# esptoy_v122.net
KiCad netlist of a schematic drawn in EAGLE
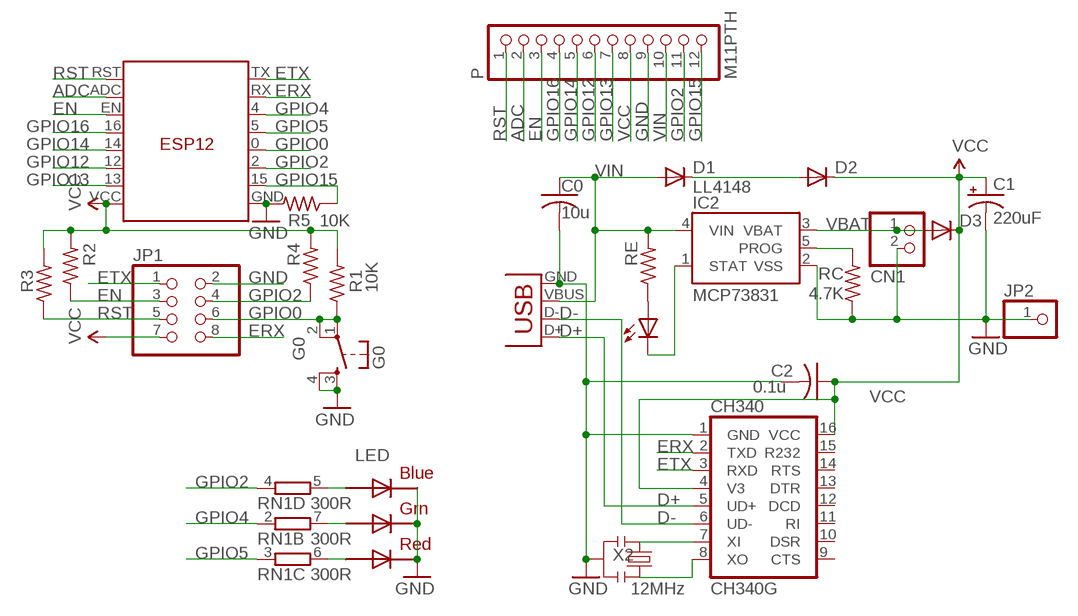
[diagram p0: schematic, sheet 1]

(export (version "E")
  (design (tool "Eeschema 10.0.6"))
  (components
    (comp (ref "C0")
      (value "10u")
      (footprint "eagle-import:C0805K")
      (libsource (lib "eagle-import") (part "adafruit2013_C-USC0805K"))
    )
    (comp (ref "C1")
      (value "220uF")
      (footprint "eagle-import:EIA7343")
      (libsource (lib "eagle-import") (part "CAP_POL7343"))
    )
    (comp (ref "C2")
      (value "0.1u")
      (footprint "eagle-import:C0603K")
      (libsource (lib "eagle-import") (part "C-USC0603K"))
    )
    (comp (ref "CH340")
      (value "CH340G")
      (footprint "eagle-import:SO16")
      (libsource (lib "eagle-import") (part "CH340G"))
    )
    (comp (ref "CHG")
      (value "0805")
      (footprint "eagle-import:CHIPLED_0805")
      (libsource (lib "eagle-import") (part "LEDCHIPLED_0805"))
    )
    (comp (ref "CN1")
      (value "JST_2PIN-SMT-RA")
      (footprint "eagle-import:JST-PH-2-SMT-RA")
      (libsource (lib "eagle-import") (part "JST_2PIN-SMT-RA"))
    )
    (comp (ref "D1")
      (value "LL4148")
      (footprint "eagle-import:SMA-DIODE")
      (libsource (lib "eagle-import") (part "DIODESMA"))
    )
    (comp (ref "D2")
      (value "DIODESMA")
      (footprint "eagle-import:SMA-DIODE")
      (libsource (lib "eagle-import") (part "DIODESMA"))
    )
    (comp (ref "D3")
      (value "DIODESMA")
      (footprint "eagle-import:SMA-DIODE")
      (libsource (lib "eagle-import") (part "DIODESMA"))
    )
    (comp (ref "G0")
      (value "G0")
      (footprint "eagle-import:TACTILE_SWITCH_SMD")
      (libsource (lib "eagle-import") (part "TAC_SWITCHSMD"))
    )
    (comp (ref "IC2")
      (value "MCP73831")
      (footprint "eagle-import:SOT23-5")
      (libsource (lib "eagle-import") (part "MCP73831"))
    )
    (comp (ref "JP1")
      (value "PINHD-2X4")
      (footprint "eagle-import:2X04")
      (libsource (lib "eagle-import") (part "PINHD-2X4"))
    )
    (comp (ref "JP2")
      (value "PINHD-1X1CB")
      (footprint "eagle-import:1X01-CLEANBIG")
      (libsource (lib "eagle-import") (part "PINHD-1X1CB"))
    )
    (comp (ref "LED")
      (value "RGBLED5050")
      (footprint "eagle-import:RGBLED5050")
      (libsource (lib "eagle-import") (part "RGBLED5050"))
    )
    (comp (ref "P")
      (value "M11PTH")
      (footprint "eagle-import:1X12-CB")
      (libsource (lib "eagle-import") (part "PINHD-1X12-CB"))
    )
    (comp (ref "R1")
      (value "10K")
      (footprint "eagle-import:R0603")
      (libsource (lib "eagle-import") (part "R-US_R0603"))
    )
    (comp (ref "R2")
      (value "R-US_R0603")
      (footprint "eagle-import:R0603")
      (libsource (lib "eagle-import") (part "R-US_R0603"))
    )
    (comp (ref "R3")
      (value "R-US_R0603")
      (footprint "eagle-import:R0603")
      (libsource (lib "eagle-import") (part "R-US_R0603"))
    )
    (comp (ref "R4")
      (value "R-US_R0603")
      (footprint "eagle-import:R0603")
      (libsource (lib "eagle-import") (part "R-US_R0603"))
    )
    (comp (ref "R5")
      (value "10K")
      (footprint "eagle-import:R0603")
      (libsource (lib "eagle-import") (part "R-US_R0603"))
    )
    (comp (ref "RC")
      (value "4.7K")
      (footprint "eagle-import:R0805")
      (libsource (lib "eagle-import") (part "adafruit2013_R-US_R0805"))
    )
    (comp (ref "RE")
      (value "R-US_R0603")
      (footprint "eagle-import:R0603")
      (libsource (lib "eagle-import") (part "R-US_R0603"))
    )
    (comp (ref "RN1")
      (value "300R")
      (footprint "eagle-import:EXB38V")
      (libsource (lib "eagle-import") (part "4R-NEXB38V"))
    )
    (comp (ref "U$1")
      (value "ESP12")
      (footprint "eagle-import:ESP12")
      (libsource (lib "eagle-import") (part "ESP12"))
    )
    (comp (ref "X1")
      (value "USBSMD")
      (footprint "eagle-import:USB-MINIB")
      (libsource (lib "eagle-import") (part "USBSMD"))
    )
    (comp (ref "X2")
      (value "12MHz")
      (footprint "eagle-import:RESONATOR-SMD")
      (libsource (lib "eagle-import") (part "RESONATORSMD"))
    )
  )
  (nets
    (net (code "1") (name "/ADC") (class "Default")
      (node (ref "P") (pin "2") (pinfunction "2_2") (pintype "passive"))
      (node (ref "U$1") (pin "ADC") (pinfunction "ADC_ADC") (pintype "bidirectional"))
    )
    (net (code "2") (name "/D+") (class "Default")
      (node (ref "CH340") (pin "5") (pinfunction "UD+_5") (pintype "bidirectional"))
      (node (ref "X1") (pin "D+") (pinfunction "D+_D+") (pintype "bidirectional"))
    )
    (net (code "3") (name "/D-") (class "Default")
      (node (ref "CH340") (pin "6") (pinfunction "UD-_6") (pintype "bidirectional"))
      (node (ref "X1") (pin "D-") (pinfunction "D-_D-") (pintype "bidirectional"))
    )
    (net (code "4") (name "/EN") (class "Default")
      (node (ref "JP1") (pin "3") (pinfunction "3_3") (pintype "passive"))
      (node (ref "P") (pin "3") (pinfunction "3_3") (pintype "passive"))
      (node (ref "R2") (pin "1") (pinfunction "1_1") (pintype "passive"))
      (node (ref "U$1") (pin "EN") (pinfunction "EN_EN") (pintype "bidirectional"))
    )
    (net (code "5") (name "/ERX") (class "Default")
      (node (ref "CH340") (pin "2") (pinfunction "TXD_2") (pintype "bidirectional"))
      (node (ref "JP1") (pin "8") (pinfunction "8_8") (pintype "passive"))
      (node (ref "U$1") (pin "RX") (pinfunction "RX_RX") (pintype "bidirectional"))
    )
    (net (code "6") (name "/ETX") (class "Default")
      (node (ref "CH340") (pin "3") (pinfunction "RXD_3") (pintype "bidirectional"))
      (node (ref "JP1") (pin "1") (pinfunction "1_1") (pintype "passive"))
      (node (ref "U$1") (pin "TX") (pinfunction "TX_TX") (pintype "bidirectional"))
    )
    (net (code "7") (name "/GPIO0") (class "Default")
      (node (ref "G0") (pin "1") (pinfunction "1_1") (pintype "passive"))
      (node (ref "G0") (pin "2") (pinfunction "2_2") (pintype "passive"))
      (node (ref "JP1") (pin "6") (pinfunction "6_6") (pintype "passive"))
      (node (ref "R1") (pin "1") (pinfunction "1_1") (pintype "passive"))
      (node (ref "U$1") (pin "0") (pinfunction "G0_0") (pintype "bidirectional"))
    )
    (net (code "8") (name "/GPIO2") (class "Default")
      (node (ref "JP1") (pin "4") (pinfunction "4_4") (pintype "passive"))
      (node (ref "P") (pin "11") (pinfunction "11_11") (pintype "passive"))
      (node (ref "R4") (pin "1") (pinfunction "1_1") (pintype "passive"))
      (node (ref "RN1") (pin "4") (pinfunction "1_4") (pintype "passive"))
      (node (ref "U$1") (pin "2") (pinfunction "G2_2") (pintype "bidirectional"))
    )
    (net (code "9") (name "/GPIO4") (class "Default")
      (node (ref "RN1") (pin "2") (pinfunction "1_2") (pintype "passive"))
      (node (ref "U$1") (pin "4") (pinfunction "G4_4") (pintype "bidirectional"))
    )
    (net (code "10") (name "/GPIO5") (class "Default")
      (node (ref "RN1") (pin "3") (pinfunction "1_3") (pintype "passive"))
      (node (ref "U$1") (pin "5") (pinfunction "G5_5") (pintype "bidirectional"))
    )
    (net (code "11") (name "/GPIO12") (class "Default")
      (node (ref "P") (pin "6") (pinfunction "6_6") (pintype "passive"))
      (node (ref "U$1") (pin "12") (pinfunction "G12_12") (pintype "bidirectional"))
    )
    (net (code "12") (name "/GPIO13") (class "Default")
      (node (ref "P") (pin "7") (pinfunction "7_7") (pintype "passive"))
      (node (ref "U$1") (pin "13") (pinfunction "G13_13") (pintype "bidirectional"))
    )
    (net (code "13") (name "/GPIO14") (class "Default")
      (node (ref "P") (pin "5") (pinfunction "5_5") (pintype "passive"))
      (node (ref "U$1") (pin "14") (pinfunction "G14_14") (pintype "bidirectional"))
    )
    (net (code "14") (name "/GPIO15") (class "Default")
      (node (ref "P") (pin "12") (pinfunction "12_12") (pintype "passive"))
      (node (ref "R5") (pin "1") (pinfunction "1_1") (pintype "passive"))
      (node (ref "U$1") (pin "15") (pinfunction "G15_15") (pintype "bidirectional"))
    )
    (net (code "15") (name "/GPIO16") (class "Default")
      (node (ref "P") (pin "4") (pinfunction "4_4") (pintype "passive"))
      (node (ref "U$1") (pin "16") (pinfunction "G16_16") (pintype "bidirectional"))
    )
    (net (code "16") (name "/RST") (class "Default")
      (node (ref "JP1") (pin "5") (pinfunction "5_5") (pintype "passive"))
      (node (ref "P") (pin "1") (pinfunction "1_1") (pintype "passive"))
      (node (ref "R3") (pin "1") (pinfunction "1_1") (pintype "passive"))
      (node (ref "U$1") (pin "RST") (pinfunction "RST_RST") (pintype "bidirectional"))
    )
    (net (code "17") (name "/VBAT") (class "Default")
      (node (ref "CN1") (pin "1") (pinfunction "2_1") (pintype "passive"))
      (node (ref "D3") (pin "A") (pinfunction "A_A") (pintype "passive"))
      (node (ref "IC2") (pin "3") (pinfunction "VBAT_3") (pintype "power_in"))
    )
    (net (code "18") (name "/VIN") (class "Default")
      (node (ref "C0") (pin "1") (pinfunction "1_1") (pintype "passive"))
      (node (ref "D1") (pin "A") (pinfunction "A_A") (pintype "passive"))
      (node (ref "IC2") (pin "4") (pinfunction "VIN_4") (pintype "power_in"))
      (node (ref "P") (pin "10") (pinfunction "10_10") (pintype "passive"))
      (node (ref "RE") (pin "2") (pinfunction "2_2") (pintype "passive"))
      (node (ref "X1") (pin "VBUS") (pinfunction "VBUS_VBUS") (pintype "bidirectional"))
    )
    (net (code "19") (name "GND") (class "Default")
      (node (ref "C0") (pin "2") (pinfunction "2_2") (pintype "passive"))
      (node (ref "C1") (pin "C") (pinfunction "-_C") (pintype "passive"))
      (node (ref "C2") (pin "2") (pinfunction "2_2") (pintype "passive"))
      (node (ref "CH340") (pin "1") (pinfunction "GND_1") (pintype "power_in"))
      (node (ref "CN1") (pin "2") (pinfunction "1_2") (pintype "passive"))
      (node (ref "G0") (pin "3") (pinfunction "3_3") (pintype "passive"))
      (node (ref "G0") (pin "4") (pinfunction "4_4") (pintype "passive"))
      (node (ref "IC2") (pin "2") (pinfunction "VSS_2") (pintype "power_in"))
      (node (ref "JP1") (pin "2") (pinfunction "2_2") (pintype "passive"))
      (node (ref "JP2") (pin "1") (pinfunction "1_1") (pintype "passive"))
      (node (ref "LED") (pin "4") (pinfunction "BLUE_C_4") (pintype "bidirectional"))
      (node (ref "LED") (pin "5") (pinfunction "RED_C_5") (pintype "bidirectional"))
      (node (ref "LED") (pin "6") (pinfunction "GREEN_C_6") (pintype "bidirectional"))
      (node (ref "P") (pin "9") (pinfunction "9_9") (pintype "passive"))
      (node (ref "R5") (pin "2") (pinfunction "2_2") (pintype "passive"))
      (node (ref "RC") (pin "1") (pinfunction "1_1") (pintype "passive"))
      (node (ref "U$1") (pin "GND") (pinfunction "GND_GND") (pintype "power_in"))
      (node (ref "X1") (pin "GND") (pinfunction "GND_GND") (pintype "bidirectional"))
      (node (ref "X2") (pin "2") (pinfunction "2_2") (pintype "passive"))
    )
    (net (code "20") (name "Net-(CH340-XI)") (class "Default")
      (node (ref "CH340") (pin "7") (pinfunction "XI_7") (pintype "bidirectional"))
      (node (ref "X2") (pin "1") (pinfunction "1_1") (pintype "passive"))
    )
    (net (code "21") (name "Net-(CH340-XO)") (class "Default")
      (node (ref "CH340") (pin "8") (pinfunction "XO_8") (pintype "bidirectional"))
      (node (ref "X2") (pin "3") (pinfunction "3_3") (pintype "passive"))
    )
    (net (code "22") (name "Net-(CHG-PadA)") (class "Default")
      (node (ref "CHG") (pin "A") (pinfunction "A_A") (pintype "passive"))
      (node (ref "RE") (pin "1") (pinfunction "1_1") (pintype "passive"))
    )
    (net (code "23") (name "Net-(D1-PadC)") (class "Default")
      (node (ref "D1") (pin "C") (pinfunction "C_C") (pintype "passive"))
      (node (ref "D2") (pin "A") (pinfunction "A_A") (pintype "passive"))
    )
    (net (code "24") (name "Net-(IC2-PROG)") (class "Default")
      (node (ref "IC2") (pin "5") (pinfunction "PROG_5") (pintype "input"))
      (node (ref "RC") (pin "2") (pinfunction "2_2") (pintype "passive"))
    )
    (net (code "25") (name "Net-(IC2-STAT)") (class "Default")
      (node (ref "CHG") (pin "C") (pinfunction "C_C") (pintype "passive"))
      (node (ref "IC2") (pin "1") (pinfunction "STAT_1") (pintype "output"))
    )
    (net (code "26") (name "Net-(LED-BLUE_A)") (class "Default")
      (node (ref "LED") (pin "3") (pinfunction "BLUE_A_3") (pintype "bidirectional"))
      (node (ref "RN1") (pin "5") (pinfunction "2_5") (pintype "passive"))
    )
    (net (code "27") (name "Net-(LED-GREEN_A)") (class "Default")
      (node (ref "LED") (pin "1") (pinfunction "GREEN_A_1") (pintype "bidirectional"))
      (node (ref "RN1") (pin "7") (pinfunction "2_7") (pintype "passive"))
    )
    (net (code "28") (name "Net-(LED-RED_A)") (class "Default")
      (node (ref "LED") (pin "2") (pinfunction "RED_A_2") (pintype "bidirectional"))
      (node (ref "RN1") (pin "6") (pinfunction "2_6") (pintype "passive"))
    )
    (net (code "29") (name "VCC") (class "Default")
      (node (ref "C1") (pin "A") (pinfunction "+_A") (pintype "passive"))
      (node (ref "C2") (pin "1") (pinfunction "1_1") (pintype "passive"))
      (node (ref "CH340") (pin "16") (pinfunction "VCC_16") (pintype "power_in"))
      (node (ref "CH340") (pin "4") (pinfunction "V3_4") (pintype "bidirectional"))
      (node (ref "D2") (pin "C") (pinfunction "C_C") (pintype "passive"))
      (node (ref "D3") (pin "C") (pinfunction "C_C") (pintype "passive"))
      (node (ref "JP1") (pin "7") (pinfunction "7_7") (pintype "passive"))
      (node (ref "P") (pin "8") (pinfunction "8_8") (pintype "passive"))
      (node (ref "R1") (pin "2") (pinfunction "2_2") (pintype "passive"))
      (node (ref "R2") (pin "2") (pinfunction "2_2") (pintype "passive"))
      (node (ref "R3") (pin "2") (pinfunction "2_2") (pintype "passive"))
      (node (ref "R4") (pin "2") (pinfunction "2_2") (pintype "passive"))
      (node (ref "U$1") (pin "VCC") (pinfunction "VCC_VCC") (pintype "power_in"))
    )
    (net (code "30") (name "unconnected-(CH340-CTS-Pad9)") (class "Default")
      (node (ref "CH340") (pin "9") (pinfunction "CTS_9") (pintype "bidirectional"))
    )
    (net (code "31") (name "unconnected-(CH340-DCD-Pad12)") (class "Default")
      (node (ref "CH340") (pin "12") (pinfunction "DCD_12") (pintype "bidirectional"))
    )
    (net (code "32") (name "unconnected-(CH340-DSR-Pad10)") (class "Default")
      (node (ref "CH340") (pin "10") (pinfunction "DSR_10") (pintype "bidirectional"))
    )
    (net (code "33") (name "unconnected-(CH340-DTR-Pad13)") (class "Default")
      (node (ref "CH340") (pin "13") (pinfunction "DTR_13") (pintype "bidirectional"))
    )
    (net (code "34") (name "unconnected-(CH340-R232-Pad15)") (class "Default")
      (node (ref "CH340") (pin "15") (pinfunction "R232_15") (pintype "bidirectional"))
    )
    (net (code "35") (name "unconnected-(CH340-RI-Pad11)") (class "Default")
      (node (ref "CH340") (pin "11") (pinfunction "RI_11") (pintype "bidirectional"))
    )
    (net (code "36") (name "unconnected-(CH340-RTS-Pad14)") (class "Default")
      (node (ref "CH340") (pin "14") (pinfunction "RTS_14") (pintype "bidirectional"))
    )
  )
)
